# PIC.net
KiCad netlist of a schematic drawn in Altium Designer
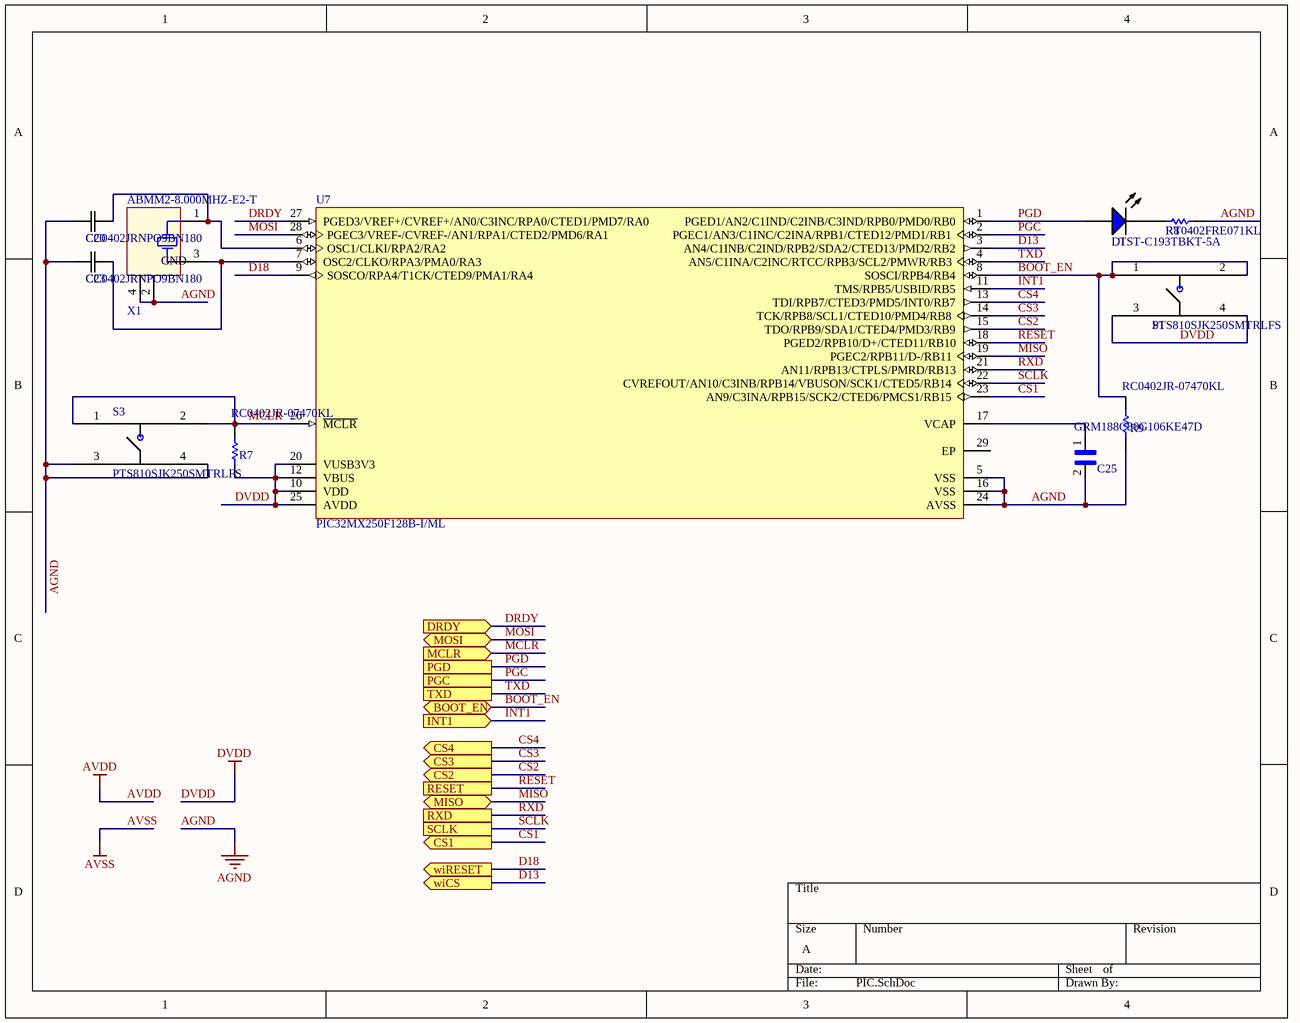
[diagram p0: PIC.SchDoc]

(export (version "E")
  (design (tool "Eeschema 10.0.6"))
  (components
    (comp (ref "C20")
      (value "CC0402JRNPO9BN180")
      (footprint "YAG_CC0402")
      (description "CAP CER 18PF 50V C0G/NPO 0402")
      (fields (field (name "TOLERANCE") "5%") (field (name "VOLTAGE") "50V"))
      (libsource (lib "EE_smallOB_BW_v1.0") (part "CC0402JRNPO9BN180"))
    )
    (comp (ref "C23")
      (value "CC0402JRNPO9BN180")
      (footprint "YAG_CC0402")
      (description "CAP CER 18PF 50V C0G/NPO 0402")
      (fields (field (name "TOLERANCE") "5%") (field (name "VOLTAGE") "50V"))
      (libsource (lib "EE_smallOB_BW_v1.0") (part "CC0402JRNPO9BN180"))
    )
    (comp (ref "C25")
      (value "GRM188C80G106KE47D")
      (footprint "*CAPC1608X90N")
      (description "CAP CER 10UF 4V X6S 0603")
      (fields (field (name "TOLERANCE") "10%"))
      (libsource (lib "EE_smallOB_BW_v1.0") (part "GRM188C80G106KE47D"))
    )
    (comp (ref "D1")
      (value "LTST-C193TBKT-5A")
      (footprint "LTST-C193TBKT_V")
      (description "LED BLUE CLEAR CHIP SMD")
      (libsource (lib "EE_smallOB_BW_v1.0") (part "LTST-C193TBKT-5A"))
    )
    (comp (ref "R7")
      (value "RC0402JR-07470KL")
      (footprint "RESC0402(1005)_N")
      (description "RES SMD 470K OHM 5% 1/16W 0402")
      (fields (field (name "TOLERANCE") "5%"))
      (libsource (lib "EE_smallOB_BW_v1.0") (part "RC0402JR-07470KL"))
    )
    (comp (ref "R8")
      (value "RT0402FRE071KL")
      (footprint "RESC1005X35X25NL10T10")
      (description "Res Thin Film 0402 1K Ohm 1% 0.063W(1/16W) ???}50ppm/???? Molded SMD Paper T/R")
      (fields (field (name "TOLERANCE") "1%"))
      (libsource (lib "EE_smallOB_BW_v1.0") (part "RT0402FRE071KL"))
    )
    (comp (ref "R9")
      (value "RC0402JR-07470KL")
      (footprint "RESC0402(1005)_N")
      (description "RES SMD 470K OHM 5% 1/16W 0402")
      (fields (field (name "TOLERANCE") "5%"))
      (libsource (lib "EE_smallOB_BW_v1.0") (part "RC0402JR-07470KL"))
    )
    (comp (ref "S1")
      (value "PTS810SJK250SMTRLFS")
      (footprint "PTS810")
      (description "SWITCH TACTILE SPST-NO 0.05A 16V")
      (libsource (lib "EE_smallOB_BW_v1.0") (part "PTS810SJK250SMTRLFS"))
    )
    (comp (ref "S3")
      (value "PTS810SJK250SMTRLFS")
      (footprint "PTS810")
      (description "SWITCH TACTILE SPST-NO 0.05A 16V")
      (libsource (lib "EE_smallOB_BW_v1.0") (part "PTS810SJK250SMTRLFS"))
    )
    (comp (ref "U7")
      (value "PIC32MX250F128B-I/ML")
      (footprint "MCHP-QFN-ML28_N")
      (description "IC MCU 32BIT 128KB FLASH 28QFN")
      (libsource (lib "EE_smallOB_BW_v1.0") (part "PIC32MX250F128B-I/ML"))
    )
    (comp (ref "X1")
      (value "ABMM2-8.000MHZ-E2-T")
      (footprint "ABRA-ABMM2-4_V")
      (description "CRYSTAL 8.0000MHZ 18PF SMD")
      (fields (field (name "TOLERANCE") "20ppm"))
      (libsource (lib "EE_smallOB_BW_v1.0") (part "ABMM2-8.000MHZ-E2-T"))
    )
  )
  (nets
    (net (code "1") (name "/BOOT_EN") (class "Default")
      (node (ref "R9") (pin "2") (pinfunction "2_2") (pintype "passive"))
      (node (ref "S1") (pin "1") (pinfunction "1_1") (pintype "passive"))
      (node (ref "S1") (pin "2") (pinfunction "2_2") (pintype "passive"))
      (node (ref "U7") (pin "8") (pinfunction "SOSCI/RPB4/RB4_8") (pintype "bidirectional"))
    )
    (net (code "2") (name "/CS1") (class "Default")
      (node (ref "U7") (pin "23") (pinfunction "AN9/C3INA/RPB15/SCK2/CTED6/PMCS1/RB15_23") (pintype "output"))
    )
    (net (code "3") (name "/CS2") (class "Default")
      (node (ref "U7") (pin "15") (pinfunction "TDO/RPB9/SDA1/CTED4/PMD3/RB9_15") (pintype "output"))
    )
    (net (code "4") (name "/CS3") (class "Default")
      (node (ref "U7") (pin "14") (pinfunction "TCK/RPB8/SCL1/CTED10/PMD4/RB8_14") (pintype "output"))
    )
    (net (code "5") (name "/CS4") (class "Default")
      (node (ref "U7") (pin "13") (pinfunction "TDI/RPB7/CTED3/PMD5/INT0/RB7_13") (pintype "output"))
    )
    (net (code "6") (name "/D13") (class "Default")
      (node (ref "U7") (pin "3") (pinfunction "AN4/C1INB/C2IND/RPB2/SDA2/CTED13/PMD2/RB2_3") (pintype "output"))
    )
    (net (code "7") (name "/D18") (class "Default")
      (node (ref "U7") (pin "9") (pinfunction "SOSCO/RPA4/T1CK/CTED9/PMA1/RA4_9") (pintype "output"))
    )
    (net (code "8") (name "/DRDY") (class "Default")
      (node (ref "U7") (pin "27") (pinfunction "PGED3/VREF+/CVREF+/AN0/C3INC/RPA0/CTED1/PMD7/RA0_27") (pintype "input"))
    )
    (net (code "9") (name "/INT1") (class "Default")
      (node (ref "U7") (pin "11") (pinfunction "TMS/RPB5/USBID/RB5_11") (pintype "input"))
    )
    (net (code "10") (name "/MCLR") (class "Default")
      (node (ref "R7") (pin "1") (pinfunction "1_1") (pintype "passive"))
      (node (ref "S3") (pin "1") (pinfunction "1_1") (pintype "passive"))
      (node (ref "S3") (pin "2") (pinfunction "2_2") (pintype "passive"))
      (node (ref "U7") (pin "26") (pinfunction "~{MCLR}_26") (pintype "input"))
    )
    (net (code "11") (name "/MISO") (class "Default")
      (node (ref "U7") (pin "19") (pinfunction "PGEC2/RPB11/D-/RB11_19") (pintype "bidirectional"))
    )
    (net (code "12") (name "/MOSI") (class "Default")
      (node (ref "U7") (pin "28") (pinfunction "PGEC3/VREF-/CVREF-/AN1/RPA1/CTED2/PMD6/RA1_28") (pintype "bidirectional"))
    )
    (net (code "13") (name "/PGC") (class "Default")
      (node (ref "U7") (pin "2") (pinfunction "PGEC1/AN3/C1INC/C2INA/RPB1/CTED12/PMD1/RB1_2") (pintype "bidirectional"))
    )
    (net (code "14") (name "/PGD") (class "Default")
      (node (ref "D1") (pin "1") (pinfunction "A_1") (pintype "passive"))
      (node (ref "U7") (pin "1") (pinfunction "PGED1/AN2/C1IND/C2INB/C3IND/RPB0/PMD0/RB0_1") (pintype "bidirectional"))
    )
    (net (code "15") (name "/RESET") (class "Default")
      (node (ref "U7") (pin "18") (pinfunction "PGED2/RPB10/D+/CTED11/RB10_18") (pintype "bidirectional"))
    )
    (net (code "16") (name "/RXD") (class "Default")
      (node (ref "U7") (pin "21") (pinfunction "AN11/RPB13/CTPLS/PMRD/RB13_21") (pintype "bidirectional"))
    )
    (net (code "17") (name "/SCLK") (class "Default")
      (node (ref "U7") (pin "22") (pinfunction "CVREFOUT/AN10/C3INB/RPB14/VBUSON/SCK1/CTED5/RB14_22") (pintype "bidirectional"))
    )
    (net (code "18") (name "/TXD") (class "Default")
      (node (ref "U7") (pin "4") (pinfunction "AN5/C1INA/C2INC/RTCC/RPB3/SCL2/PMWR/RB3_4") (pintype "bidirectional"))
    )
    (net (code "19") (name "AGND") (class "Default")
      (node (ref "C20") (pin "1") (pinfunction "1_1") (pintype "passive"))
      (node (ref "C23") (pin "1") (pinfunction "1_1") (pintype "passive"))
      (node (ref "C25") (pin "2") (pinfunction "2_2") (pintype "passive"))
      (node (ref "R8") (pin "2") (pinfunction "2_2") (pintype "passive"))
      (node (ref "R9") (pin "1") (pinfunction "1_1") (pintype "passive"))
      (node (ref "S3") (pin "3") (pinfunction "3_3") (pintype "passive"))
      (node (ref "S3") (pin "4") (pinfunction "4_4") (pintype "passive"))
      (node (ref "U7") (pin "16") (pinfunction "VSS_16") (pintype "power_in"))
      (node (ref "U7") (pin "24") (pinfunction "AVSS_24") (pintype "power_in"))
      (node (ref "U7") (pin "5") (pinfunction "VSS_5") (pintype "power_in"))
      (node (ref "X1") (pin "2") (pinfunction "GND_2") (pintype "power_in"))
      (node (ref "X1") (pin "4") (pinfunction "GND_4") (pintype "power_in"))
    )
    (net (code "22") (name "DVDD") (class "Default")
      (node (ref "R7") (pin "2") (pinfunction "2_2") (pintype "passive"))
      (node (ref "S1") (pin "3") (pinfunction "3_3") (pintype "passive"))
      (node (ref "S1") (pin "4") (pinfunction "4_4") (pintype "passive"))
      (node (ref "U7") (pin "10") (pinfunction "VDD_10") (pintype "power_in"))
      (node (ref "U7") (pin "12") (pinfunction "VBUS_12") (pintype "power_in"))
      (node (ref "U7") (pin "20") (pinfunction "VUSB3V3_20") (pintype "power_in"))
      (node (ref "U7") (pin "25") (pinfunction "AVDD_25") (pintype "power_in"))
    )
    (net (code "23") (name "Net-(D1-K)") (class "Default")
      (node (ref "D1") (pin "2") (pinfunction "K_2") (pintype "passive"))
      (node (ref "R8") (pin "1") (pinfunction "1_1") (pintype "passive"))
    )
    (net (code "24") (name "Net-(U7-OSC1{slash}CLKI{slash}RPA2{slash}RA2)") (class "Default")
      (node (ref "C20") (pin "2") (pinfunction "2_2") (pintype "passive"))
      (node (ref "U7") (pin "6") (pinfunction "OSC1/CLKI/RPA2/RA2_6") (pintype "bidirectional"))
      (node (ref "X1") (pin "1") (pinfunction "X1_1") (pintype "passive"))
    )
    (net (code "25") (name "Net-(U7-OSC2{slash}CLKO{slash}RPA3{slash}PMA0{slash}RA3)") (class "Default")
      (node (ref "C23") (pin "2") (pinfunction "2_2") (pintype "passive"))
      (node (ref "U7") (pin "7") (pinfunction "OSC2/CLKO/RPA3/PMA0/RA3_7") (pintype "bidirectional"))
      (node (ref "X1") (pin "3") (pinfunction "X2_3") (pintype "passive"))
    )
    (net (code "26") (name "Net-(U7-VCAP)") (class "Default")
      (node (ref "C25") (pin "1") (pinfunction "1_1") (pintype "passive"))
      (node (ref "U7") (pin "17") (pinfunction "VCAP_17") (pintype "passive"))
    )
    (net (code "27") (name "unconnected-(U7-EP-Pad29)") (class "Default")
      (node (ref "U7") (pin "29") (pinfunction "EP_29") (pintype "power_in"))
    )
  )
)
